# Adafruit_RGB_Matrix_Bonnet.net
KiCad netlist of a schematic drawn in EAGLE
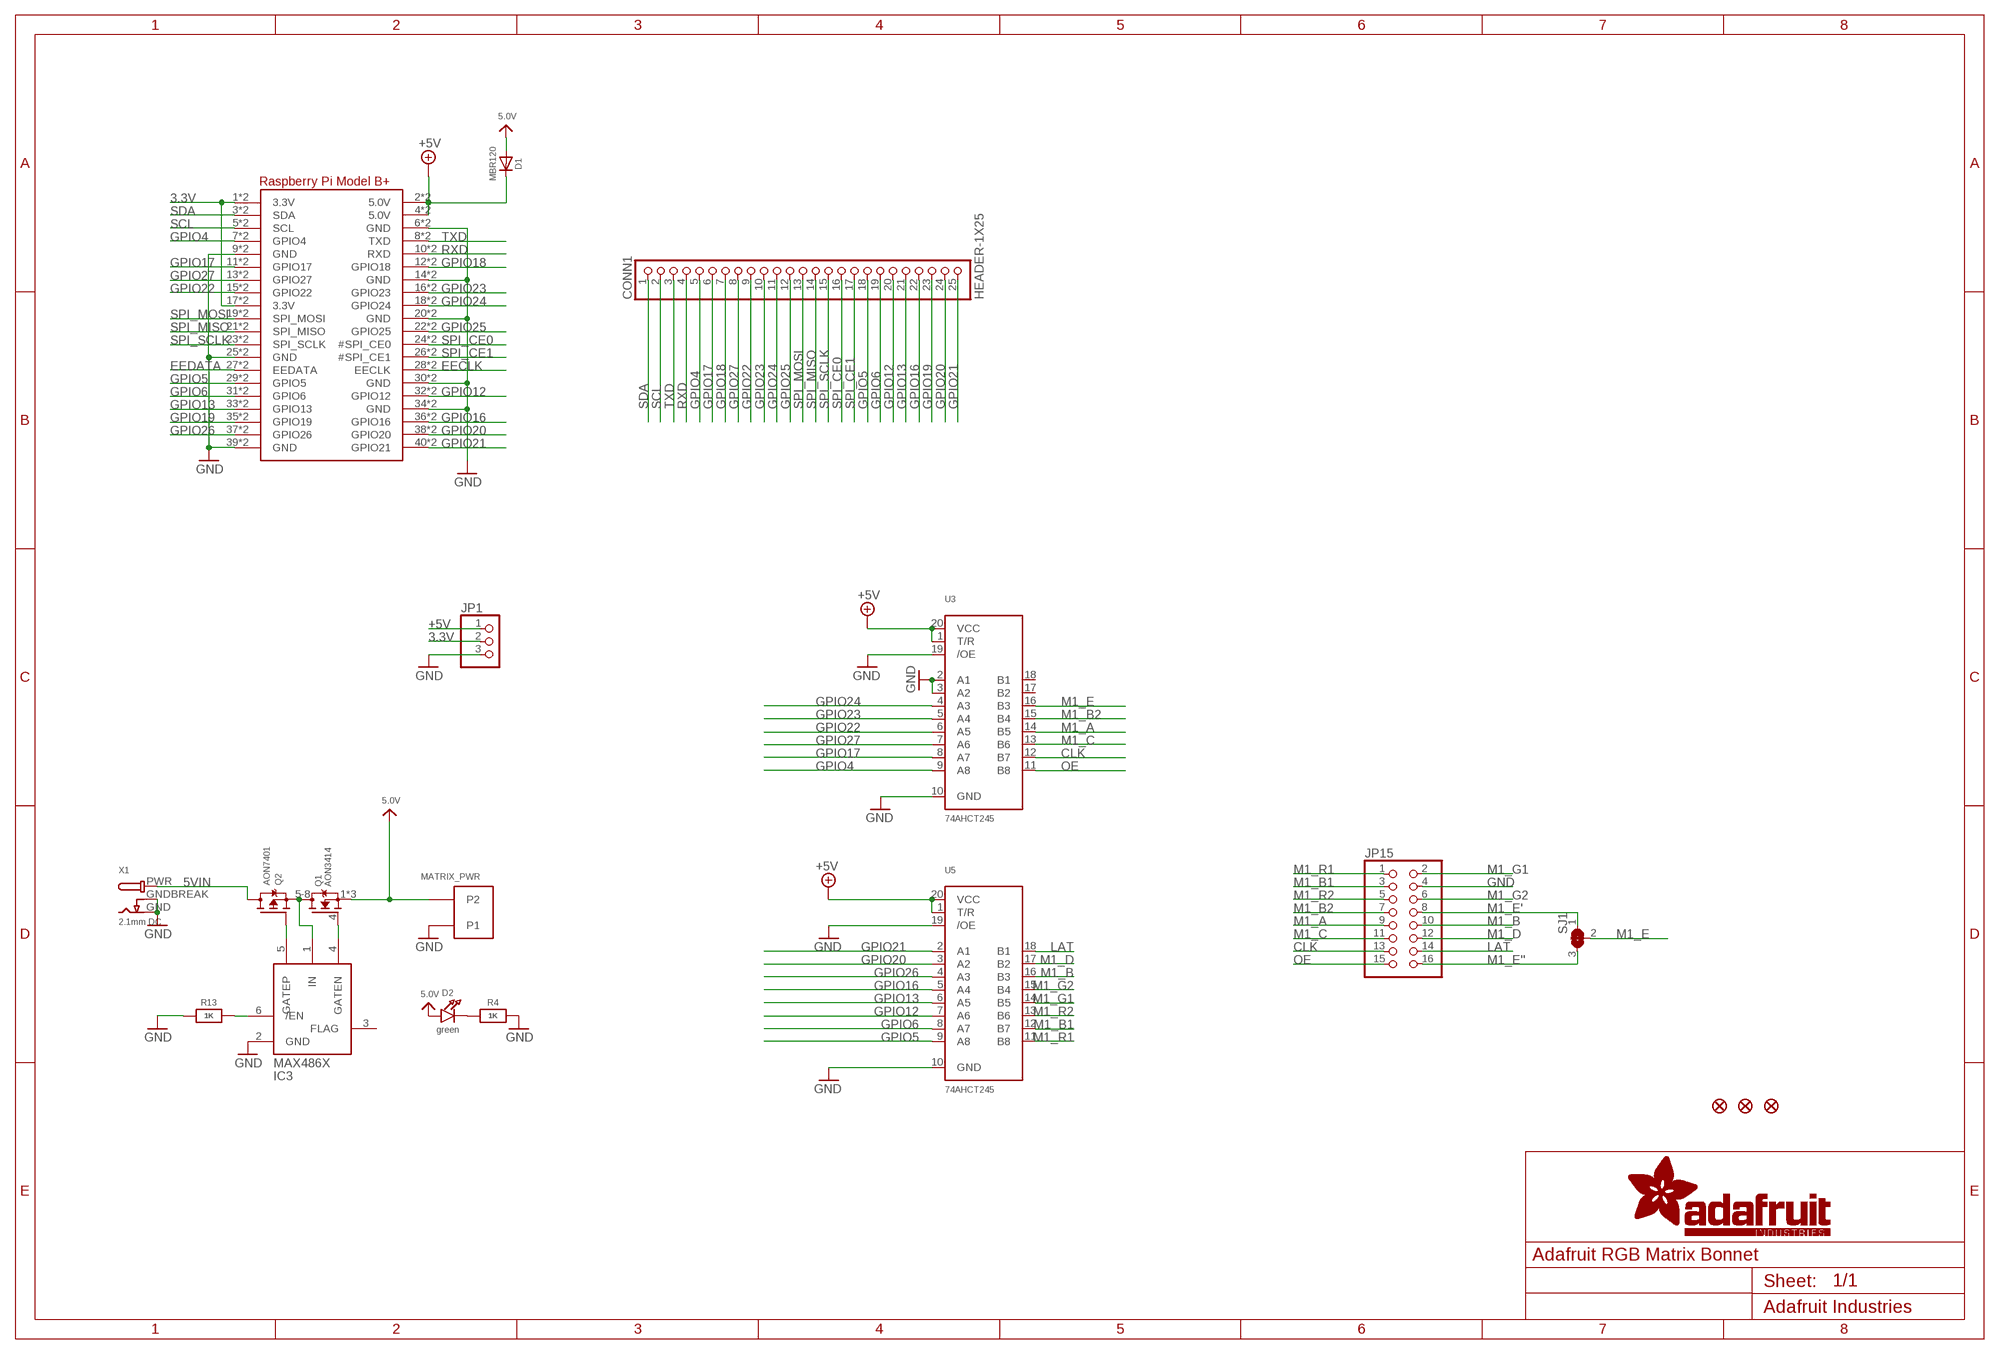
[diagram p0: schematic, sheet 1]

(export (version "E")
  (design (tool "Eeschema 10.0.6"))
  (components
    (comp (ref "CONN1")
      (value "HEADER-1X25")
      (footprint "eagle-import:1X25_ROUND_70MIL")
      (libsource (lib "eagle-import") (part "HEADER-1X25"))
    )
    (comp (ref "D1")
      (value "MBR120")
      (footprint "eagle-import:SOD-123")
      (libsource (lib "eagle-import") (part "DIODESOD-123"))
    )
    (comp (ref "D2")
      (value "green")
      (footprint "eagle-import:CHIPLED_0805_NOOUTLINE")
      (libsource (lib "eagle-import") (part "LED0805_NOOUTLINE"))
    )
    (comp (ref "FID1")
      (value "FIDUCIAL_1MM")
      (footprint "eagle-import:FIDUCIAL_1MM")
      (libsource (lib "eagle-import") (part "FIDUCIAL_1MM"))
    )
    (comp (ref "FID2")
      (value "FIDUCIAL_1MM")
      (footprint "eagle-import:FIDUCIAL_1MM")
      (libsource (lib "eagle-import") (part "FIDUCIAL_1MM"))
    )
    (comp (ref "FID3")
      (value "FIDUCIAL_1MM")
      (footprint "eagle-import:FIDUCIAL_1MM")
      (libsource (lib "eagle-import") (part "FIDUCIAL_1MM"))
    )
    (comp (ref "IC3")
      (value "MAX4866T")
      (footprint "eagle-import:SOT23-6")
      (libsource (lib "eagle-import") (part "MAX486X/SOT"))
    )
    (comp (ref "JP1")
      (value "HEADER-1X376MIL")
      (footprint "eagle-import:1X03_ROUND_76")
      (libsource (lib "eagle-import") (part "HEADER-1X376MIL"))
    )
    (comp (ref "JP15")
      (value "HEADER-2X8_SHROUDED")
      (footprint "eagle-import:2X08_SHROUDED")
      (libsource (lib "eagle-import") (part "HEADER-2X8_SHROUDED"))
    )
    (comp (ref "MATRIX_PWR")
      (value "PINHEAD")
      (footprint "eagle-import:TERMBLOCK508")
      (libsource (lib "eagle-import") (part "PINHEAD"))
    )
    (comp (ref "Q1")
      (value "AON3414")
      (footprint "eagle-import:POWERPAK-1212-8")
      (libsource (lib "eagle-import") (part "MOSFET-NPOWERPAK-1212-8"))
    )
    (comp (ref "Q2")
      (value "AON7401")
      (footprint "eagle-import:POWERDI3333")
      (libsource (lib "eagle-import") (part "MOSFET-P-POWERDI3333"))
    )
    (comp (ref "R4")
      (value "1K")
      (footprint "eagle-import:0805-NO")
      (libsource (lib "eagle-import") (part "RESISTOR0805_NOOUTLINE"))
    )
    (comp (ref "R13")
      (value "1K")
      (footprint "eagle-import:0805-NO")
      (libsource (lib "eagle-import") (part "RESISTOR0805_NOOUTLINE"))
    )
    (comp (ref "RPI1")
      (value "RASPBERRYPI_BPLUS_BONNET_THMSMT")
      (footprint "eagle-import:PI_BONNET_THMSMT")
      (libsource (lib "eagle-import") (part "RASPBERRYPI_BPLUS_BONNET_THMSMT"))
    )
    (comp (ref "SJ1")
      (value "SOLDERJUMPER_2WAY")
      (footprint "eagle-import:SOLDERJUMPER_2WAY_OPEN_NOPASTE")
      (libsource (lib "eagle-import") (part "SOLDERJUMPER_2WAY"))
    )
    (comp (ref "U3")
      (value "74AHCT245")
      (footprint "eagle-import:TSSOP20")
      (libsource (lib "eagle-import") (part "74LCX245"))
    )
    (comp (ref "U5")
      (value "74AHCT245")
      (footprint "eagle-import:TSSOP20")
      (libsource (lib "eagle-import") (part "74LCX245"))
    )
    (comp (ref "X1")
      (value "2.1mm DC")
      (footprint "eagle-import:DCJACK_2MM_PTH")
      (libsource (lib "eagle-import") (part "DCBARRELPTH"))
    )
  )
  (nets
    (net (code "1") (name "+5V") (class "Default")
      (node (ref "D1") (pin "C") (pinfunction "C_C") (pintype "passive"))
      (node (ref "JP1") (pin "1") (pinfunction "1_1") (pintype "passive"))
      (node (ref "RPI1") (pin "2") (pinfunction "5.0V_2") (pintype "power_in"))
      (node (ref "RPI1") (pin "4") (pinfunction "5.0V_4") (pintype "power_in"))
      (node (ref "RPI1") (pin "S2") (pinfunction "5.0V_S2") (pintype "power_in"))
      (node (ref "RPI1") (pin "S4") (pinfunction "5.0V_S4") (pintype "power_in"))
      (node (ref "U3") (pin "1") (pinfunction "T/R_1") (pintype "bidirectional"))
      (node (ref "U3") (pin "20") (pinfunction "VCC_20") (pintype "bidirectional"))
      (node (ref "U5") (pin "1") (pinfunction "T/R_1") (pintype "bidirectional"))
      (node (ref "U5") (pin "20") (pinfunction "VCC_20") (pintype "bidirectional"))
    )
    (net (code "2") (name "/3.3V") (class "Default")
      (node (ref "JP1") (pin "2") (pinfunction "2_2") (pintype "passive"))
      (node (ref "RPI1") (pin "1") (pinfunction "3.3V_1") (pintype "power_in"))
      (node (ref "RPI1") (pin "17") (pinfunction "3.3V_17") (pintype "power_in"))
      (node (ref "RPI1") (pin "S1") (pinfunction "3.3V_S1") (pintype "power_in"))
      (node (ref "RPI1") (pin "S17") (pinfunction "3.3V_S17") (pintype "power_in"))
    )
    (net (code "3") (name "/5VIN") (class "Default")
      (node (ref "Q2") (pin "5678") (pinfunction "D_5678") (pintype "passive"))
      (node (ref "X1") (pin "PWR") (pinfunction "PWR_PWR") (pintype "power_in"))
    )
    (net (code "4") (name "/CLK") (class "Default")
      (node (ref "JP15") (pin "13") (pinfunction "13_13") (pintype "passive"))
      (node (ref "U3") (pin "12") (pinfunction "B7_12") (pintype "bidirectional"))
    )
    (net (code "5") (name "/EECLK") (class "Default")
      (node (ref "RPI1") (pin "28") (pinfunction "EECLK_28") (pintype "bidirectional"))
      (node (ref "RPI1") (pin "S28") (pinfunction "EECLK_S28") (pintype "bidirectional"))
    )
    (net (code "6") (name "/EEDATA") (class "Default")
      (node (ref "RPI1") (pin "27") (pinfunction "EEDATA_27") (pintype "bidirectional"))
      (node (ref "RPI1") (pin "S27") (pinfunction "EEDATA_S27") (pintype "bidirectional"))
    )
    (net (code "7") (name "/GPIO4") (class "Default")
      (node (ref "CONN1") (pin "5") (pinfunction "5_5") (pintype "passive"))
      (node (ref "RPI1") (pin "7") (pinfunction "GPIO4_7") (pintype "bidirectional"))
      (node (ref "RPI1") (pin "S7") (pinfunction "GPIO4_S7") (pintype "bidirectional"))
      (node (ref "U3") (pin "9") (pinfunction "A8_9") (pintype "bidirectional"))
    )
    (net (code "8") (name "/GPIO5") (class "Default")
      (node (ref "CONN1") (pin "18") (pinfunction "18_18") (pintype "passive"))
      (node (ref "RPI1") (pin "29") (pinfunction "GPIO5_29") (pintype "bidirectional"))
      (node (ref "RPI1") (pin "S29") (pinfunction "GPIO5_S29") (pintype "bidirectional"))
      (node (ref "U5") (pin "9") (pinfunction "A8_9") (pintype "bidirectional"))
    )
    (net (code "9") (name "/GPIO6") (class "Default")
      (node (ref "CONN1") (pin "19") (pinfunction "19_19") (pintype "passive"))
      (node (ref "RPI1") (pin "31") (pinfunction "GPIO6_31") (pintype "bidirectional"))
      (node (ref "RPI1") (pin "S31") (pinfunction "GPIO6_S31") (pintype "bidirectional"))
      (node (ref "U5") (pin "8") (pinfunction "A7_8") (pintype "bidirectional"))
    )
    (net (code "10") (name "/GPIO12") (class "Default")
      (node (ref "CONN1") (pin "20") (pinfunction "20_20") (pintype "passive"))
      (node (ref "RPI1") (pin "32") (pinfunction "GPIO12_32") (pintype "bidirectional"))
      (node (ref "RPI1") (pin "S32") (pinfunction "GPIO12_S32") (pintype "bidirectional"))
      (node (ref "U5") (pin "7") (pinfunction "A6_7") (pintype "bidirectional"))
    )
    (net (code "11") (name "/GPIO13") (class "Default")
      (node (ref "CONN1") (pin "21") (pinfunction "21_21") (pintype "passive"))
      (node (ref "RPI1") (pin "33") (pinfunction "GPIO13_33") (pintype "bidirectional"))
      (node (ref "RPI1") (pin "S33") (pinfunction "GPIO13_S33") (pintype "bidirectional"))
      (node (ref "U5") (pin "6") (pinfunction "A5_6") (pintype "bidirectional"))
    )
    (net (code "12") (name "/GPIO16") (class "Default")
      (node (ref "CONN1") (pin "22") (pinfunction "22_22") (pintype "passive"))
      (node (ref "RPI1") (pin "36") (pinfunction "GPIO16_36") (pintype "bidirectional"))
      (node (ref "RPI1") (pin "S36") (pinfunction "GPIO16_S36") (pintype "bidirectional"))
      (node (ref "U5") (pin "5") (pinfunction "A4_5") (pintype "bidirectional"))
    )
    (net (code "13") (name "/GPIO17") (class "Default")
      (node (ref "CONN1") (pin "6") (pinfunction "6_6") (pintype "passive"))
      (node (ref "RPI1") (pin "11") (pinfunction "GPIO17_11") (pintype "bidirectional"))
      (node (ref "RPI1") (pin "S11") (pinfunction "GPIO17_S11") (pintype "bidirectional"))
      (node (ref "U3") (pin "8") (pinfunction "A7_8") (pintype "bidirectional"))
    )
    (net (code "14") (name "/GPIO18") (class "Default")
      (node (ref "CONN1") (pin "7") (pinfunction "7_7") (pintype "passive"))
      (node (ref "RPI1") (pin "12") (pinfunction "GPIO18_12") (pintype "bidirectional"))
      (node (ref "RPI1") (pin "S12") (pinfunction "GPIO18_S12") (pintype "bidirectional"))
    )
    (net (code "15") (name "/GPIO19") (class "Default")
      (node (ref "CONN1") (pin "23") (pinfunction "23_23") (pintype "passive"))
      (node (ref "RPI1") (pin "35") (pinfunction "GPIO19_35") (pintype "bidirectional"))
      (node (ref "RPI1") (pin "S35") (pinfunction "GPIO19_S35") (pintype "bidirectional"))
    )
    (net (code "16") (name "/GPIO20") (class "Default")
      (node (ref "CONN1") (pin "24") (pinfunction "24_24") (pintype "passive"))
      (node (ref "RPI1") (pin "38") (pinfunction "GPIO20_38") (pintype "bidirectional"))
      (node (ref "RPI1") (pin "S38") (pinfunction "GPIO20_S38") (pintype "bidirectional"))
      (node (ref "U5") (pin "3") (pinfunction "A2_3") (pintype "bidirectional"))
    )
    (net (code "17") (name "/GPIO21") (class "Default")
      (node (ref "CONN1") (pin "25") (pinfunction "25_25") (pintype "passive"))
      (node (ref "RPI1") (pin "40") (pinfunction "GPIO21_40") (pintype "bidirectional"))
      (node (ref "RPI1") (pin "S40") (pinfunction "GPIO21_S40") (pintype "bidirectional"))
      (node (ref "U5") (pin "2") (pinfunction "A1_2") (pintype "bidirectional"))
    )
    (net (code "18") (name "/GPIO22") (class "Default")
      (node (ref "CONN1") (pin "9") (pinfunction "9_9") (pintype "passive"))
      (node (ref "RPI1") (pin "15") (pinfunction "GPIO22_15") (pintype "bidirectional"))
      (node (ref "RPI1") (pin "S15") (pinfunction "GPIO22_S15") (pintype "bidirectional"))
      (node (ref "U3") (pin "6") (pinfunction "A5_6") (pintype "bidirectional"))
    )
    (net (code "19") (name "/GPIO23") (class "Default")
      (node (ref "CONN1") (pin "10") (pinfunction "10_10") (pintype "passive"))
      (node (ref "RPI1") (pin "16") (pinfunction "GPIO23_16") (pintype "bidirectional"))
      (node (ref "RPI1") (pin "S16") (pinfunction "GPIO23_S16") (pintype "bidirectional"))
      (node (ref "U3") (pin "5") (pinfunction "A4_5") (pintype "bidirectional"))
    )
    (net (code "20") (name "/GPIO24") (class "Default")
      (node (ref "CONN1") (pin "11") (pinfunction "11_11") (pintype "passive"))
      (node (ref "RPI1") (pin "18") (pinfunction "GPIO24_18") (pintype "bidirectional"))
      (node (ref "RPI1") (pin "S18") (pinfunction "GPIO24_S18") (pintype "bidirectional"))
      (node (ref "U3") (pin "4") (pinfunction "A3_4") (pintype "bidirectional"))
    )
    (net (code "21") (name "/GPIO25") (class "Default")
      (node (ref "CONN1") (pin "12") (pinfunction "12_12") (pintype "passive"))
      (node (ref "RPI1") (pin "22") (pinfunction "GPIO25_22") (pintype "bidirectional"))
      (node (ref "RPI1") (pin "S22") (pinfunction "GPIO25_S22") (pintype "bidirectional"))
    )
    (net (code "22") (name "/GPIO26") (class "Default")
      (node (ref "RPI1") (pin "37") (pinfunction "GPIO26_37") (pintype "bidirectional"))
      (node (ref "RPI1") (pin "S37") (pinfunction "GPIO26_S37") (pintype "bidirectional"))
      (node (ref "U5") (pin "4") (pinfunction "A3_4") (pintype "bidirectional"))
    )
    (net (code "23") (name "/GPIO27") (class "Default")
      (node (ref "CONN1") (pin "8") (pinfunction "8_8") (pintype "passive"))
      (node (ref "RPI1") (pin "13") (pinfunction "GPIO27_13") (pintype "bidirectional"))
      (node (ref "RPI1") (pin "S13") (pinfunction "GPIO27_S13") (pintype "bidirectional"))
      (node (ref "U3") (pin "7") (pinfunction "A6_7") (pintype "bidirectional"))
    )
    (net (code "24") (name "/LAT") (class "Default")
      (node (ref "JP15") (pin "14") (pinfunction "14_14") (pintype "passive"))
      (node (ref "U5") (pin "18") (pinfunction "B1_18") (pintype "bidirectional"))
    )
    (net (code "25") (name "/M1_A") (class "Default")
      (node (ref "JP15") (pin "9") (pinfunction "9_9") (pintype "passive"))
      (node (ref "U3") (pin "14") (pinfunction "B5_14") (pintype "bidirectional"))
    )
    (net (code "26") (name "/M1_B") (class "Default")
      (node (ref "JP15") (pin "10") (pinfunction "10_10") (pintype "passive"))
      (node (ref "U5") (pin "16") (pinfunction "B3_16") (pintype "bidirectional"))
    )
    (net (code "27") (name "/M1_B1") (class "Default")
      (node (ref "JP15") (pin "3") (pinfunction "3_3") (pintype "passive"))
      (node (ref "U5") (pin "12") (pinfunction "B7_12") (pintype "bidirectional"))
    )
    (net (code "28") (name "/M1_B2") (class "Default")
      (node (ref "JP15") (pin "7") (pinfunction "7_7") (pintype "passive"))
      (node (ref "U3") (pin "15") (pinfunction "B4_15") (pintype "bidirectional"))
    )
    (net (code "29") (name "/M1_C") (class "Default")
      (node (ref "JP15") (pin "11") (pinfunction "11_11") (pintype "passive"))
      (node (ref "U3") (pin "13") (pinfunction "B6_13") (pintype "bidirectional"))
    )
    (net (code "30") (name "/M1_D") (class "Default")
      (node (ref "JP15") (pin "12") (pinfunction "12_12") (pintype "passive"))
      (node (ref "U5") (pin "17") (pinfunction "B2_17") (pintype "bidirectional"))
    )
    (net (code "31") (name "/M1_E") (class "Default")
      (node (ref "SJ1") (pin "2") (pinfunction "2_2") (pintype "passive"))
      (node (ref "U3") (pin "16") (pinfunction "B3_16") (pintype "bidirectional"))
    )
    (net (code "32") (name "/M1_E'") (class "Default")
      (node (ref "JP15") (pin "8") (pinfunction "8_8") (pintype "passive"))
      (node (ref "SJ1") (pin "1") (pinfunction "1_1") (pintype "passive"))
    )
    (net (code "33") (name "/M1_E''") (class "Default")
      (node (ref "JP15") (pin "16") (pinfunction "16_16") (pintype "passive"))
      (node (ref "SJ1") (pin "3") (pinfunction "3_3") (pintype "passive"))
    )
    (net (code "34") (name "/M1_G1") (class "Default")
      (node (ref "JP15") (pin "2") (pinfunction "2_2") (pintype "passive"))
      (node (ref "U5") (pin "14") (pinfunction "B5_14") (pintype "bidirectional"))
    )
    (net (code "35") (name "/M1_G2") (class "Default")
      (node (ref "JP15") (pin "6") (pinfunction "6_6") (pintype "passive"))
      (node (ref "U5") (pin "15") (pinfunction "B4_15") (pintype "bidirectional"))
    )
    (net (code "36") (name "/M1_R1") (class "Default")
      (node (ref "JP15") (pin "1") (pinfunction "1_1") (pintype "passive"))
      (node (ref "U5") (pin "11") (pinfunction "B8_11") (pintype "bidirectional"))
    )
    (net (code "37") (name "/M1_R2") (class "Default")
      (node (ref "JP15") (pin "5") (pinfunction "5_5") (pintype "passive"))
      (node (ref "U5") (pin "13") (pinfunction "B6_13") (pintype "bidirectional"))
    )
    (net (code "38") (name "/OE") (class "Default")
      (node (ref "JP15") (pin "15") (pinfunction "15_15") (pintype "passive"))
      (node (ref "U3") (pin "11") (pinfunction "B8_11") (pintype "bidirectional"))
    )
    (net (code "39") (name "/RXD") (class "Default")
      (node (ref "CONN1") (pin "4") (pinfunction "4_4") (pintype "passive"))
      (node (ref "RPI1") (pin "10") (pinfunction "RXD_10") (pintype "bidirectional"))
      (node (ref "RPI1") (pin "S10") (pinfunction "RXD_S10") (pintype "bidirectional"))
    )
    (net (code "40") (name "/SCL") (class "Default")
      (node (ref "CONN1") (pin "2") (pinfunction "2_2") (pintype "passive"))
      (node (ref "RPI1") (pin "5") (pinfunction "SCL_5") (pintype "bidirectional"))
      (node (ref "RPI1") (pin "S5") (pinfunction "SCL_S5") (pintype "bidirectional"))
    )
    (net (code "41") (name "/SDA") (class "Default")
      (node (ref "CONN1") (pin "1") (pinfunction "1_1") (pintype "passive"))
      (node (ref "RPI1") (pin "3") (pinfunction "SDA_3") (pintype "bidirectional"))
      (node (ref "RPI1") (pin "S3") (pinfunction "SDA_S3") (pintype "bidirectional"))
    )
    (net (code "42") (name "/SPI_CE0") (class "Default")
      (node (ref "CONN1") (pin "16") (pinfunction "16_16") (pintype "passive"))
      (node (ref "RPI1") (pin "24") (pinfunction "#SPI_CE0_24") (pintype "bidirectional"))
      (node (ref "RPI1") (pin "S24") (pinfunction "#SPI_CE0_S24") (pintype "bidirectional"))
    )
    (net (code "43") (name "/SPI_CE1") (class "Default")
      (node (ref "CONN1") (pin "17") (pinfunction "17_17") (pintype "passive"))
      (node (ref "RPI1") (pin "26") (pinfunction "#SPI_CE1_26") (pintype "bidirectional"))
      (node (ref "RPI1") (pin "S26") (pinfunction "#SPI_CE1_S26") (pintype "bidirectional"))
    )
    (net (code "44") (name "/SPI_MISO") (class "Default")
      (node (ref "CONN1") (pin "14") (pinfunction "14_14") (pintype "passive"))
      (node (ref "RPI1") (pin "21") (pinfunction "SPI_MISO_21") (pintype "bidirectional"))
      (node (ref "RPI1") (pin "S21") (pinfunction "SPI_MISO_S21") (pintype "bidirectional"))
    )
    (net (code "45") (name "/SPI_MOSI") (class "Default")
      (node (ref "CONN1") (pin "13") (pinfunction "13_13") (pintype "passive"))
      (node (ref "RPI1") (pin "19") (pinfunction "SPI_MOSI_19") (pintype "bidirectional"))
      (node (ref "RPI1") (pin "S19") (pinfunction "SPI_MOSI_S19") (pintype "bidirectional"))
    )
    (net (code "46") (name "/SPI_SCLK") (class "Default")
      (node (ref "CONN1") (pin "15") (pinfunction "15_15") (pintype "passive"))
      (node (ref "RPI1") (pin "23") (pinfunction "SPI_SCLK_23") (pintype "bidirectional"))
      (node (ref "RPI1") (pin "S23") (pinfunction "SPI_SCLK_S23") (pintype "bidirectional"))
    )
    (net (code "47") (name "/TXD") (class "Default")
      (node (ref "CONN1") (pin "3") (pinfunction "3_3") (pintype "passive"))
      (node (ref "RPI1") (pin "8") (pinfunction "TXD_8") (pintype "bidirectional"))
      (node (ref "RPI1") (pin "S8") (pinfunction "TXD_S8") (pintype "bidirectional"))
    )
    (net (code "48") (name "5.0V") (class "Default")
      (node (ref "D1") (pin "A") (pinfunction "A_A") (pintype "passive"))
      (node (ref "D2") (pin "A") (pinfunction "A_A") (pintype "passive"))
      (node (ref "MATRIX_PWR") (pin "P$4") (pinfunction "P2_P$4") (pintype "bidirectional"))
      (node (ref "Q1") (pin "1") (pinfunction "S_1") (pintype "bidirectional"))
      (node (ref "Q1") (pin "2") (pinfunction "S_2") (pintype "bidirectional"))
      (node (ref "Q1") (pin "3") (pinfunction "S_3") (pintype "bidirectional"))
    )
    (net (code "49") (name "GND") (class "Default")
      (node (ref "IC3") (pin "2") (pinfunction "GND_2") (pintype "power_in"))
      (node (ref "JP1") (pin "3") (pinfunction "3_3") (pintype "passive"))
      (node (ref "JP15") (pin "4") (pinfunction "4_4") (pintype "passive"))
      (node (ref "MATRIX_PWR") (pin "P$3") (pinfunction "P1_P$3") (pintype "bidirectional"))
      (node (ref "R13") (pin "1") (pinfunction "1_1") (pintype "passive"))
      (node (ref "R4") (pin "2") (pinfunction "2_2") (pintype "passive"))
      (node (ref "RPI1") (pin "14") (pinfunction "GND_14") (pintype "power_in"))
      (node (ref "RPI1") (pin "20") (pinfunction "GND_20") (pintype "power_in"))
      (node (ref "RPI1") (pin "25") (pinfunction "GND_25") (pintype "power_in"))
      (node (ref "RPI1") (pin "30") (pinfunction "GND_30") (pintype "power_in"))
      (node (ref "RPI1") (pin "34") (pinfunction "GND_34") (pintype "power_in"))
      (node (ref "RPI1") (pin "39") (pinfunction "GND_39") (pintype "power_in"))
      (node (ref "RPI1") (pin "6") (pinfunction "GND_6") (pintype "power_in"))
      (node (ref "RPI1") (pin "9") (pinfunction "GND_9") (pintype "power_in"))
      (node (ref "RPI1") (pin "S14") (pinfunction "GND_S14") (pintype "power_in"))
      (node (ref "RPI1") (pin "S20") (pinfunction "GND_S20") (pintype "power_in"))
      (node (ref "RPI1") (pin "S25") (pinfunction "GND_S25") (pintype "power_in"))
      (node (ref "RPI1") (pin "S30") (pinfunction "GND_S30") (pintype "power_in"))
      (node (ref "RPI1") (pin "S34") (pinfunction "GND_S34") (pintype "power_in"))
      (node (ref "RPI1") (pin "S39") (pinfunction "GND_S39") (pintype "power_in"))
      (node (ref "RPI1") (pin "S6") (pinfunction "GND_S6") (pintype "power_in"))
      (node (ref "RPI1") (pin "S9") (pinfunction "GND_S9") (pintype "power_in"))
      (node (ref "U3") (pin "10") (pinfunction "GND_10") (pintype "bidirectional"))
      (node (ref "U3") (pin "19") (pinfunction "/OE_19") (pintype "bidirectional"))
      (node (ref "U3") (pin "2") (pinfunction "A1_2") (pintype "bidirectional"))
      (node (ref "U3") (pin "3") (pinfunction "A2_3") (pintype "bidirectional"))
      (node (ref "U5") (pin "10") (pinfunction "GND_10") (pintype "bidirectional"))
      (node (ref "U5") (pin "19") (pinfunction "/OE_19") (pintype "bidirectional"))
      (node (ref "X1") (pin "GND") (pinfunction "GND_GND") (pintype "power_in"))
      (node (ref "X1") (pin "GNDBREAK") (pinfunction "GNDBREAK_GNDBREAK") (pintype "power_in"))
    )
    (net (code "50") (name "Net-(D2-PadC)") (class "Default")
      (node (ref "D2") (pin "C") (pinfunction "C_C") (pintype "passive"))
      (node (ref "R4") (pin "1") (pinfunction "1_1") (pintype "passive"))
    )
    (net (code "51") (name "Net-(IC3-GATEN)") (class "Default")
      (node (ref "IC3") (pin "4") (pinfunction "GATEN_4") (pintype "output"))
      (node (ref "Q1") (pin "4") (pinfunction "G_4") (pintype "bidirectional"))
    )
    (net (code "52") (name "Net-(IC3-GATEP)") (class "Default")
      (node (ref "IC3") (pin "5") (pinfunction "GATEP_5") (pintype "output"))
      (node (ref "Q2") (pin "4") (pinfunction "G_4") (pintype "passive"))
    )
    (net (code "53") (name "Net-(IC3-IN)") (class "Default")
      (node (ref "IC3") (pin "1") (pinfunction "IN_1") (pintype "input"))
      (node (ref "Q1") (pin "5-8") (pinfunction "D_5-8") (pintype "bidirectional"))
      (node (ref "Q2") (pin "1") (pinfunction "S_1") (pintype "passive"))
      (node (ref "Q2") (pin "2") (pinfunction "S_2") (pintype "passive"))
      (node (ref "Q2") (pin "3") (pinfunction "S_3") (pintype "passive"))
    )
    (net (code "54") (name "Net-(IC3-{slash}EN)") (class "Default")
      (node (ref "IC3") (pin "6") (pinfunction "/EN_6") (pintype "input"))
      (node (ref "R13") (pin "2") (pinfunction "2_2") (pintype "passive"))
    )
    (net (code "55") (name "unconnected-(IC3-FLAG-Pad3)") (class "Default")
      (node (ref "IC3") (pin "3") (pinfunction "FLAG_3") (pintype "output"))
    )
    (net (code "56") (name "unconnected-(U3-B1-Pad18)") (class "Default")
      (node (ref "U3") (pin "18") (pinfunction "B1_18") (pintype "bidirectional"))
    )
    (net (code "57") (name "unconnected-(U3-B2-Pad17)") (class "Default")
      (node (ref "U3") (pin "17") (pinfunction "B2_17") (pintype "bidirectional"))
    )
  )
)
